# Ideal_Diode_B.net
KiCad netlist of a schematic drawn in Altium Designer
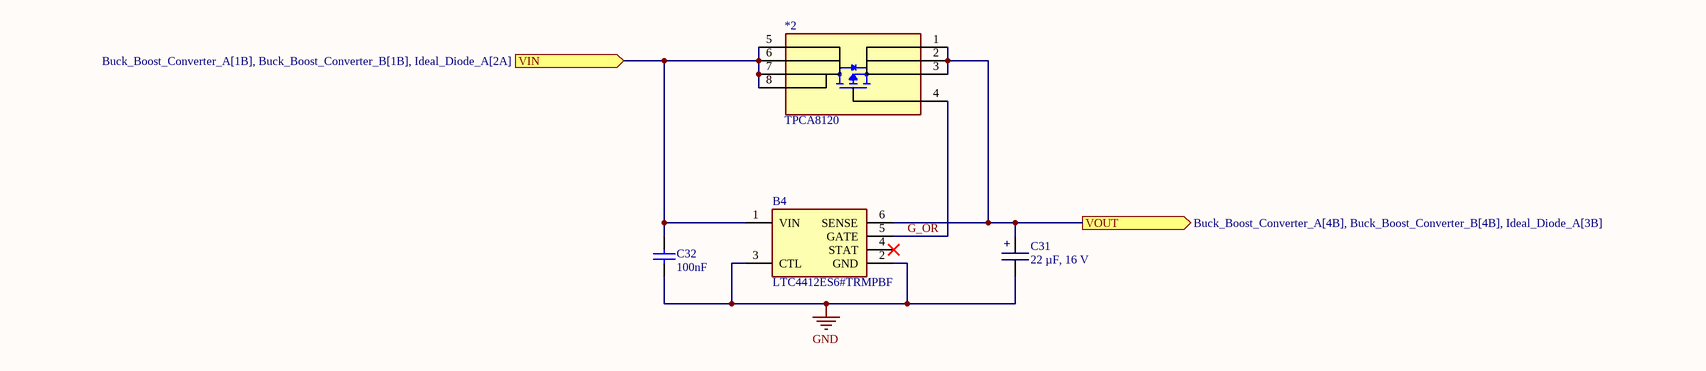
[diagram p0: Ideal_Diode_B.SchDoc]

(export (version "E")
  (design (tool "Eeschema 10.0.6"))
  (components
    (comp (ref "*2")
      (value "TPCA8120")
      (footprint "TRANS_TPHR8504PL,L1Q")
      (libsource (lib "EPS_Board_Lib") (part "TPCA8120"))
    )
    (comp (ref "B4")
      (value "LTC4412ES6#TRMPBF")
      (footprint "SOT95P280X100-6N")
      (description "Hot Swap Controller LTC4412ES6#TRMPBF, Positive Voltage, 2.5  28 V, TSOT-23, 6-Pin")
      (fields (field (name "MOUSER PART NUMBER") "584-LTC4412ES6TRMPBF"))
      (libsource (lib "EPS_Board_Lib") (part "LTC4412ES6"))
    )
    (comp (ref "C31")
      (value "22 µF, 16 V")
      (footprint "TANTALUM SMD C")
      (description "CAP TANT 22uF 10% 16V 2312")
      (libsource (lib "Altium_Tanta_Capacitor") (part "01231222610"))
    )
    (comp (ref "C32")
      (value "100nF")
      (footprint "CAP-SM-0805")
      (description "Capacitor")
      (fields (field (name "Comment") "Cap Non-Pol SMD"))
      (libsource (lib "PIF_Library") (part "Cap Non-Pol SMD"))
    )
  )
  (nets
    (net (code "1") (name "/G_OR") (class "Default")
      (node (ref "*2") (pin "4") (pinfunction "G_4") (pintype "passive"))
      (node (ref "B4") (pin "5") (pinfunction "GATE_5") (pintype "passive"))
    )
    (net (code "2") (name "/VIN") (class "Default")
      (node (ref "*2") (pin "5") (pinfunction "D1_5") (pintype "passive"))
      (node (ref "*2") (pin "6") (pinfunction "D2_6") (pintype "passive"))
      (node (ref "*2") (pin "7") (pinfunction "D3_7") (pintype "passive"))
      (node (ref "*2") (pin "8") (pinfunction "D4_8") (pintype "passive"))
      (node (ref "B4") (pin "1") (pinfunction "VIN_1") (pintype "passive"))
      (node (ref "C32") (pin "2") (pinfunction "2_2") (pintype "passive"))
    )
    (net (code "3") (name "/VOUT") (class "Default")
      (node (ref "*2") (pin "1") (pinfunction "S1_1") (pintype "passive"))
      (node (ref "*2") (pin "2") (pinfunction "S2_2") (pintype "power_in"))
      (node (ref "*2") (pin "3") (pinfunction "S3_3") (pintype "passive"))
      (node (ref "B4") (pin "6") (pinfunction "SENSE_6") (pintype "passive"))
      (node (ref "C31") (pin "2") (pinfunction "2_2") (pintype "passive"))
    )
    (net (code "4") (name "GND") (class "Default")
      (node (ref "B4") (pin "2") (pinfunction "GND_2") (pintype "passive"))
      (node (ref "B4") (pin "3") (pinfunction "CTL_3") (pintype "passive"))
      (node (ref "C31") (pin "1") (pinfunction "1_1") (pintype "passive"))
      (node (ref "C32") (pin "1") (pinfunction "1_1") (pintype "passive"))
    )
    (net (code "5") (name "unconnected-(B4-STAT-Pad4)") (class "Default")
      (node (ref "B4") (pin "4") (pinfunction "STAT_4") (pintype "passive+no_connect"))
    )
  )
)
